# DAPule-LPC11U35-v1_1_0.net
KiCad netlist of a schematic drawn in EAGLE
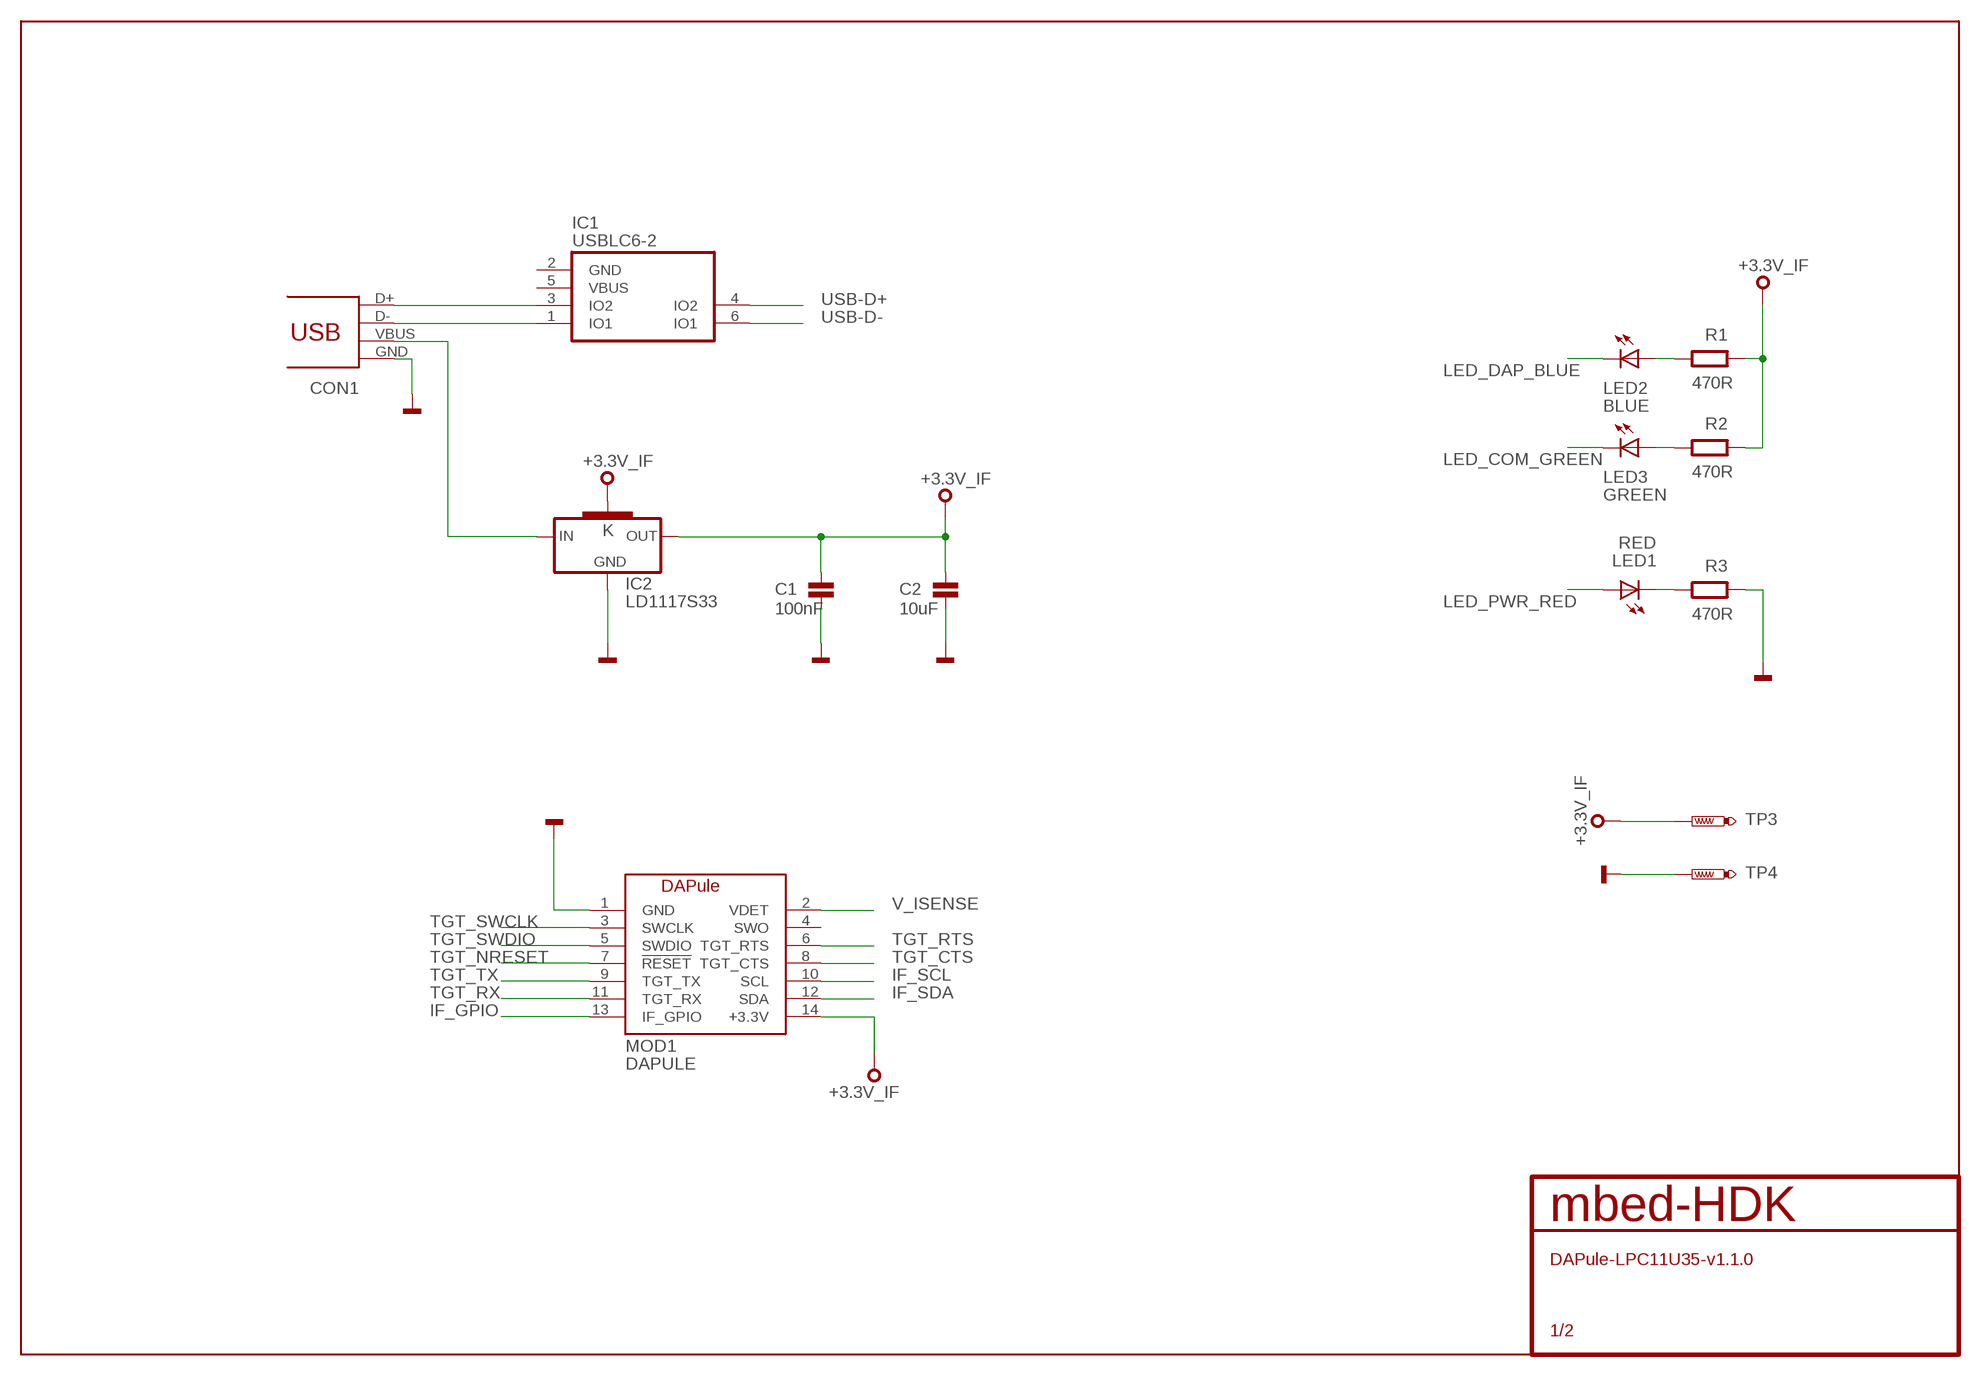
[diagram p0: schematic, sheet 1]
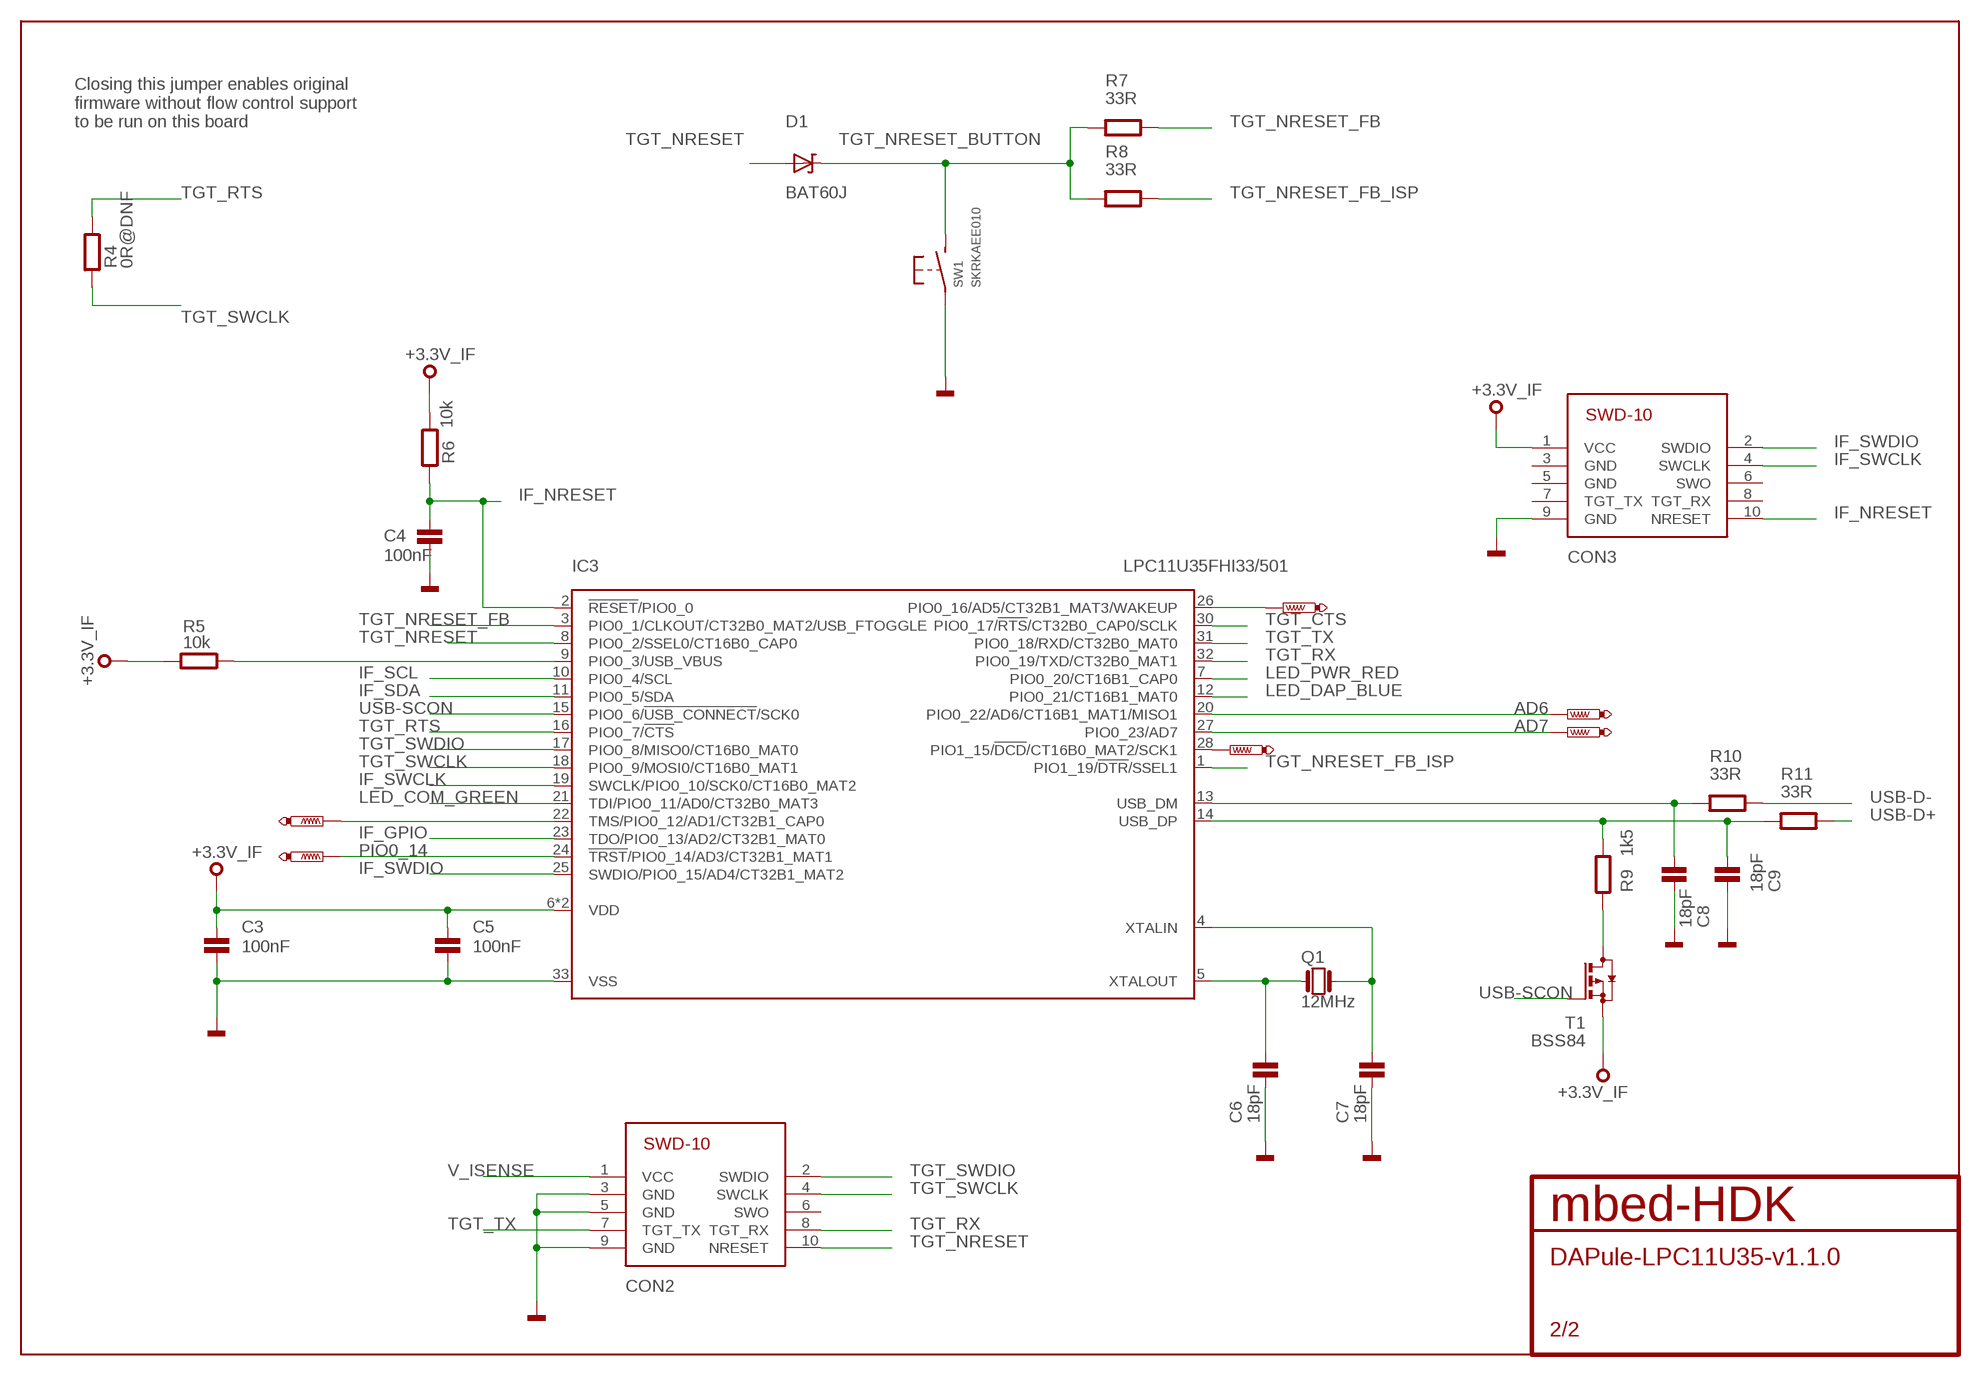
[diagram p1: schematic, sheet 2]

(export (version "E")
  (design (tool "Eeschema 10.0.6"))
  (components
    (comp (ref "C3")
      (value "100nF")
      (footprint "eagle-import:0603")
      (libsource (lib "eagle-import") (part "C0603"))
    )
    (comp (ref "C4")
      (value "100nF")
      (footprint "eagle-import:0603")
      (libsource (lib "eagle-import") (part "C0603"))
    )
    (comp (ref "C5")
      (value "100nF")
      (footprint "eagle-import:0603")
      (libsource (lib "eagle-import") (part "C0603"))
    )
    (comp (ref "C6")
      (value "18pF")
      (footprint "eagle-import:0603")
      (libsource (lib "eagle-import") (part "C0603"))
    )
    (comp (ref "C7")
      (value "18pF")
      (footprint "eagle-import:0603")
      (libsource (lib "eagle-import") (part "C0603"))
    )
    (comp (ref "C8")
      (value "18pF")
      (footprint "eagle-import:0603")
      (libsource (lib "eagle-import") (part "C0603"))
    )
    (comp (ref "C9")
      (value "18pF")
      (footprint "eagle-import:0603")
      (libsource (lib "eagle-import") (part "C0603"))
    )
    (comp (ref "CON2")
      (value "SWD-10/TC2050_SMD")
      (footprint "eagle-import:FTSH-105-02")
      (libsource (lib "eagle-import") (part "SWD-10/TC2050_SMD"))
    )
    (comp (ref "CON3")
      (value "SWD-10/TC2050_SMD")
      (footprint "eagle-import:FTSH-105-02")
      (libsource (lib "eagle-import") (part "SWD-10/TC2050_SMD"))
    )
    (comp (ref "D1")
      (value "BAT60J")
      (footprint "eagle-import:SOD323")
      (fields (field (name "MF") "STMicroelectronics"))
      (libsource (lib "eagle-import") (part "BAT60J"))
    )
    (comp (ref "IC3")
      (value "LPC11U35FHI33/501")
      (footprint "eagle-import:SOT617-3")
      (libsource (lib "eagle-import") (part "LPC11U35FHI33/501"))
    )
    (comp (ref "Q1")
      (value "12MHz")
      (footprint "eagle-import:3.2X.2.5")
      (libsource (lib "eagle-import") (part "Q_3.2X2.5"))
    )
    (comp (ref "R4")
      (value "0R@DNF")
      (footprint "eagle-import:0402@1")
      (libsource (lib "eagle-import") (part "R0402"))
    )
    (comp (ref "R5")
      (value "10k")
      (footprint "eagle-import:0603@1")
      (libsource (lib "eagle-import") (part "R0603"))
    )
    (comp (ref "R6")
      (value "10k")
      (footprint "eagle-import:0603@1")
      (libsource (lib "eagle-import") (part "R0603"))
    )
    (comp (ref "R7")
      (value "33R")
      (footprint "eagle-import:0603@1")
      (libsource (lib "eagle-import") (part "R0603"))
    )
    (comp (ref "R8")
      (value "33R")
      (footprint "eagle-import:0603@1")
      (libsource (lib "eagle-import") (part "R0603"))
    )
    (comp (ref "R9")
      (value "1k5")
      (footprint "eagle-import:0603@1")
      (libsource (lib "eagle-import") (part "R0603"))
    )
    (comp (ref "R10")
      (value "33R")
      (footprint "eagle-import:0603@1")
      (libsource (lib "eagle-import") (part "R0603"))
    )
    (comp (ref "R11")
      (value "33R")
      (footprint "eagle-import:0603@1")
      (libsource (lib "eagle-import") (part "R0603"))
    )
    (comp (ref "SW1")
      (value "SKRKAEE010")
      (footprint "eagle-import:SKRKAEE010")
      (fields (field (name "MF") "ALPS"))
      (libsource (lib "eagle-import") (part "SKRKAEE010"))
    )
    (comp (ref "T1")
      (value "BSS84")
      (footprint "eagle-import:SOT23")
      (libsource (lib "eagle-import") (part "BSS84"))
    )
    (comp (ref "TP1")
      (value "PTR1TP07R")
      (footprint "eagle-import:TP07R")
      (libsource (lib "eagle-import") (part "PTR1TP07R"))
    )
    (comp (ref "TP2")
      (value "PTR1TP07R")
      (footprint "eagle-import:TP07R")
      (libsource (lib "eagle-import") (part "PTR1TP07R"))
    )
    (comp (ref "TP5")
      (value "PTR1TP07R")
      (footprint "eagle-import:TP07R")
      (libsource (lib "eagle-import") (part "PTR1TP07R"))
    )
    (comp (ref "TP8")
      (value "PTR1TP07R")
      (footprint "eagle-import:TP07R")
      (libsource (lib "eagle-import") (part "PTR1TP07R"))
    )
    (comp (ref "TP9")
      (value "PTR1TP07R")
      (footprint "eagle-import:TP07R")
      (libsource (lib "eagle-import") (part "PTR1TP07R"))
    )
    (comp (ref "TP13")
      (value "PTR1TP07R")
      (footprint "eagle-import:TP07R")
      (libsource (lib "eagle-import") (part "PTR1TP07R"))
    )
    (comp (ref "C1")
      (value "100nF")
      (footprint "eagle-import:0603")
      (libsource (lib "eagle-import") (part "C0603"))
    )
    (comp (ref "C2")
      (value "10uF")
      (footprint "eagle-import:0603")
      (libsource (lib "eagle-import") (part "C0603"))
    )
    (comp (ref "CON1")
      (value "USB_MICROB")
      (footprint "eagle-import:MOLEX-47364-0001")
      (libsource (lib "eagle-import") (part "USB_MICROB"))
    )
    (comp (ref "IC1")
      (value "USBLC6-2SC6")
      (footprint "eagle-import:SOT23-6L")
      (libsource (lib "eagle-import") (part "USBLC6-2SC6"))
    )
    (comp (ref "IC2")
      (value "LD1117S33")
      (footprint "eagle-import:SOT223")
      (libsource (lib "eagle-import") (part "LD1117S33"))
    )
    (comp (ref "LED1")
      (value "RED")
      (footprint "eagle-import:CHIPLED_0603")
      (libsource (lib "eagle-import") (part "LED0603"))
    )
    (comp (ref "LED2")
      (value "BLUE")
      (footprint "eagle-import:CHIPLED_0603")
      (libsource (lib "eagle-import") (part "LED0603"))
    )
    (comp (ref "LED3")
      (value "GREEN")
      (footprint "eagle-import:CHIPLED_0603")
      (libsource (lib "eagle-import") (part "LED0603"))
    )
    (comp (ref "MOD1")
      (value "DAPULE")
      (footprint "eagle-import:DAPULE")
      (libsource (lib "eagle-import") (part "DAPULE"))
    )
    (comp (ref "R1")
      (value "470R")
      (footprint "eagle-import:0603@1")
      (libsource (lib "eagle-import") (part "R0603"))
    )
    (comp (ref "R2")
      (value "470R")
      (footprint "eagle-import:0603@1")
      (libsource (lib "eagle-import") (part "R0603"))
    )
    (comp (ref "R3")
      (value "470R")
      (footprint "eagle-import:0603@1")
      (libsource (lib "eagle-import") (part "R0603"))
    )
    (comp (ref "TP3")
      (value "TEST-POINT-50R-PTH")
      (footprint "eagle-import:TP50-PTH")
      (libsource (lib "eagle-import") (part "TEST-POINT-50R-PTH"))
    )
    (comp (ref "TP4")
      (value "TEST-POINT-50R-PTH")
      (footprint "eagle-import:TP50-PTH")
      (libsource (lib "eagle-import") (part "TEST-POINT-50R-PTH"))
    )
  )
  (nets
    (net (code "1") (name "+3.3V_IF") (class "Default")
      (node (ref "C1") (pin "1") (pinfunction "P$1_1") (pintype "passive"))
      (node (ref "C2") (pin "1") (pinfunction "P$1_1") (pintype "passive"))
      (node (ref "C3") (pin "1") (pinfunction "P$1_1") (pintype "passive"))
      (node (ref "C5") (pin "1") (pinfunction "P$1_1") (pintype "passive"))
      (node (ref "CON3") (pin "1") (pinfunction "VCC_1") (pintype "bidirectional"))
      (node (ref "IC2") (pin "2") (pinfunction "OUT_2") (pintype "passive"))
      (node (ref "IC2") (pin "4") (pinfunction "K_4") (pintype "passive"))
      (node (ref "IC3") (pin "29") (pinfunction "VDD_29") (pintype "passive"))
      (node (ref "IC3") (pin "6") (pinfunction "VDD_6") (pintype "passive"))
      (node (ref "MOD1") (pin "14") (pinfunction "+3.3V_14") (pintype "bidirectional"))
      (node (ref "R1") (pin "1") (pinfunction "P$1_1") (pintype "passive"))
      (node (ref "R2") (pin "1") (pinfunction "P$1_1") (pintype "passive"))
      (node (ref "R5") (pin "2") (pinfunction "P$2_2") (pintype "passive"))
      (node (ref "R6") (pin "2") (pinfunction "P$2_2") (pintype "passive"))
      (node (ref "T1") (pin "2") (pinfunction "S_2") (pintype "passive"))
      (node (ref "TP3") (pin "TP") (pinfunction "TP_TP") (pintype "input"))
    )
    (net (code "2") (name "AD6") (class "Default")
      (node (ref "IC3") (pin "20") (pinfunction "PIO0_22/AD6/CT16B1_MAT1/MISO1_20") (pintype "bidirectional"))
      (node (ref "TP9") (pin "TP") (pinfunction "TP_TP") (pintype "input"))
    )
    (net (code "3") (name "AD7") (class "Default")
      (node (ref "IC3") (pin "27") (pinfunction "PIO0_23/AD7_27") (pintype "bidirectional"))
      (node (ref "TP8") (pin "TP") (pinfunction "TP_TP") (pintype "input"))
    )
    (net (code "4") (name "GND") (class "Default")
      (node (ref "C1") (pin "2") (pinfunction "P$2_2") (pintype "passive"))
      (node (ref "C2") (pin "2") (pinfunction "P$2_2") (pintype "passive"))
      (node (ref "C3") (pin "2") (pinfunction "P$2_2") (pintype "passive"))
      (node (ref "C4") (pin "2") (pinfunction "P$2_2") (pintype "passive"))
      (node (ref "C5") (pin "2") (pinfunction "P$2_2") (pintype "passive"))
      (node (ref "C6") (pin "2") (pinfunction "P$2_2") (pintype "passive"))
      (node (ref "C7") (pin "2") (pinfunction "P$2_2") (pintype "passive"))
      (node (ref "C8") (pin "2") (pinfunction "P$2_2") (pintype "passive"))
      (node (ref "C9") (pin "2") (pinfunction "P$2_2") (pintype "passive"))
      (node (ref "CON1") (pin "GND") (pinfunction "GND_GND") (pintype "bidirectional"))
      (node (ref "CON2") (pin "3") (pinfunction "GND_3") (pintype "bidirectional"))
      (node (ref "CON2") (pin "5") (pinfunction "GND_5") (pintype "bidirectional"))
      (node (ref "CON2") (pin "9") (pinfunction "GND_9") (pintype "bidirectional"))
      (node (ref "CON3") (pin "9") (pinfunction "GND_9") (pintype "bidirectional"))
      (node (ref "IC2") (pin "1") (pinfunction "GND_1") (pintype "input"))
      (node (ref "IC3") (pin "33") (pinfunction "VSS_33") (pintype "passive"))
      (node (ref "MOD1") (pin "1") (pinfunction "GND_1") (pintype "bidirectional"))
      (node (ref "R3") (pin "1") (pinfunction "P$1_1") (pintype "passive"))
      (node (ref "SW1") (pin "P$1") (pinfunction "P_P$1") (pintype "passive"))
      (node (ref "TP4") (pin "TP") (pinfunction "TP_TP") (pintype "input"))
    )
    (net (code "5") (name "IF_GPIO") (class "Default")
      (node (ref "IC3") (pin "23") (pinfunction "TDO/PIO0_13/AD2/CT32B1_MAT0_23") (pintype "bidirectional"))
      (node (ref "MOD1") (pin "13") (pinfunction "IF_GPIO_13") (pintype "bidirectional"))
    )
    (net (code "6") (name "IF_NRESET") (class "Default")
      (node (ref "C4") (pin "1") (pinfunction "P$1_1") (pintype "passive"))
      (node (ref "CON3") (pin "10") (pinfunction "NRESET_10") (pintype "bidirectional"))
      (node (ref "IC3") (pin "2") (pinfunction "~{RESET}/PIO0_0_2") (pintype "bidirectional"))
      (node (ref "R6") (pin "1") (pinfunction "P$1_1") (pintype "passive"))
    )
    (net (code "7") (name "IF_SCL") (class "Default")
      (node (ref "IC3") (pin "10") (pinfunction "PIO0_4/SCL_10") (pintype "bidirectional"))
      (node (ref "MOD1") (pin "10") (pinfunction "SCL_10") (pintype "bidirectional"))
    )
    (net (code "8") (name "IF_SDA") (class "Default")
      (node (ref "IC3") (pin "11") (pinfunction "PIO0_5/SDA_11") (pintype "bidirectional"))
      (node (ref "MOD1") (pin "12") (pinfunction "SDA_12") (pintype "bidirectional"))
    )
    (net (code "9") (name "IF_SWCLK") (class "Default")
      (node (ref "CON3") (pin "4") (pinfunction "SWCLK_4") (pintype "bidirectional"))
      (node (ref "IC3") (pin "19") (pinfunction "SWCLK/PIO0_10/SCK0/CT16B0_MAT2_19") (pintype "bidirectional"))
    )
    (net (code "10") (name "IF_SWDIO") (class "Default")
      (node (ref "CON3") (pin "2") (pinfunction "SWDIO_2") (pintype "bidirectional"))
      (node (ref "IC3") (pin "25") (pinfunction "SWDIO/PIO0_15/AD4/CT32B1_MAT2_25") (pintype "bidirectional"))
    )
    (net (code "11") (name "LED_COM_GREEN") (class "Default")
      (node (ref "IC3") (pin "21") (pinfunction "TDI/PIO0_11/AD0/CT32B0_MAT3_21") (pintype "bidirectional"))
      (node (ref "LED3") (pin "C") (pinfunction "C_C") (pintype "passive"))
    )
    (net (code "12") (name "LED_DAP_BLUE") (class "Default")
      (node (ref "IC3") (pin "12") (pinfunction "PIO0_21/CT16B1_MAT0_12") (pintype "bidirectional"))
      (node (ref "LED2") (pin "C") (pinfunction "C_C") (pintype "passive"))
    )
    (net (code "13") (name "LED_PWR_RED") (class "Default")
      (node (ref "IC3") (pin "7") (pinfunction "PIO0_20/CT16B1_CAP0_7") (pintype "bidirectional"))
      (node (ref "LED1") (pin "A") (pinfunction "A_A") (pintype "passive"))
    )
    (net (code "14") (name "Net-(C6-P$1)") (class "Default")
      (node (ref "C6") (pin "1") (pinfunction "P$1_1") (pintype "passive"))
      (node (ref "IC3") (pin "5") (pinfunction "XTALOUT_5") (pintype "output"))
      (node (ref "Q1") (pin "P$1") (pinfunction "1_P$1") (pintype "passive"))
    )
    (net (code "15") (name "Net-(C7-P$1)") (class "Default")
      (node (ref "C7") (pin "1") (pinfunction "P$1_1") (pintype "passive"))
      (node (ref "IC3") (pin "4") (pinfunction "XTALIN_4") (pintype "input"))
      (node (ref "Q1") (pin "P$3") (pinfunction "2_P$3") (pintype "passive"))
    )
    (net (code "16") (name "Net-(C8-P$1)") (class "Default")
      (node (ref "C8") (pin "1") (pinfunction "P$1_1") (pintype "passive"))
      (node (ref "IC3") (pin "13") (pinfunction "USB_DM_13") (pintype "bidirectional"))
      (node (ref "R10") (pin "2") (pinfunction "P$2_2") (pintype "passive"))
    )
    (net (code "17") (name "Net-(C9-P$1)") (class "Default")
      (node (ref "C9") (pin "1") (pinfunction "P$1_1") (pintype "passive"))
      (node (ref "IC3") (pin "14") (pinfunction "USB_DP_14") (pintype "bidirectional"))
      (node (ref "R11") (pin "2") (pinfunction "P$2_2") (pintype "passive"))
      (node (ref "R9") (pin "2") (pinfunction "P$2_2") (pintype "passive"))
    )
    (net (code "18") (name "Net-(CON1-PadD+)") (class "Default")
      (node (ref "CON1") (pin "D+") (pinfunction "D+_D+") (pintype "bidirectional"))
      (node (ref "IC1") (pin "3") (pinfunction "IO2_3") (pintype "bidirectional"))
    )
    (net (code "19") (name "Net-(CON1-PadD-)") (class "Default")
      (node (ref "CON1") (pin "D-") (pinfunction "D-_D-") (pintype "bidirectional"))
      (node (ref "IC1") (pin "1") (pinfunction "IO1_1") (pintype "bidirectional"))
    )
    (net (code "20") (name "Net-(IC2-IN)") (class "Default")
      (node (ref "CON1") (pin "VBUS") (pinfunction "VBUS_VBUS") (pintype "bidirectional"))
      (node (ref "IC2") (pin "3") (pinfunction "IN_3") (pintype "input"))
    )
    (net (code "21") (name "Net-(IC3-PIO0_3{slash}USB_VBUS)") (class "Default")
      (node (ref "IC3") (pin "9") (pinfunction "PIO0_3/USB_VBUS_9") (pintype "bidirectional"))
      (node (ref "R5") (pin "1") (pinfunction "P$1_1") (pintype "passive"))
    )
    (net (code "22") (name "Net-(IC3-PIO0_16{slash}AD5{slash}CT32B1_MAT3{slash}WAKEUP)") (class "Default")
      (node (ref "IC3") (pin "26") (pinfunction "PIO0_16/AD5/CT32B1_MAT3/WAKEUP_26") (pintype "bidirectional"))
      (node (ref "TP2") (pin "TP") (pinfunction "TP_TP") (pintype "input"))
    )
    (net (code "23") (name "Net-(IC3-PIO1_15{slash}~{DCD}{slash}CT16B0_MAT2{slash}SCK1)") (class "Default")
      (node (ref "IC3") (pin "28") (pinfunction "PIO1_15/~{DCD}/CT16B0_MAT2/SCK1_28") (pintype "bidirectional"))
      (node (ref "TP5") (pin "TP") (pinfunction "TP_TP") (pintype "input"))
    )
    (net (code "24") (name "Net-(IC3-TMS{slash}PIO0_12{slash}AD1{slash}CT32B1_CAP0)") (class "Default")
      (node (ref "IC3") (pin "22") (pinfunction "TMS/PIO0_12/AD1/CT32B1_CAP0_22") (pintype "bidirectional"))
      (node (ref "TP1") (pin "TP") (pinfunction "TP_TP") (pintype "input"))
    )
    (net (code "25") (name "Net-(R1-P$2)") (class "Default")
      (node (ref "LED2") (pin "A") (pinfunction "A_A") (pintype "passive"))
      (node (ref "R1") (pin "2") (pinfunction "P$2_2") (pintype "passive"))
    )
    (net (code "26") (name "Net-(R2-P$2)") (class "Default")
      (node (ref "LED3") (pin "A") (pinfunction "A_A") (pintype "passive"))
      (node (ref "R2") (pin "2") (pinfunction "P$2_2") (pintype "passive"))
    )
    (net (code "27") (name "Net-(R3-P$2)") (class "Default")
      (node (ref "LED1") (pin "C") (pinfunction "C_C") (pintype "passive"))
      (node (ref "R3") (pin "2") (pinfunction "P$2_2") (pintype "passive"))
    )
    (net (code "28") (name "Net-(R9-P$1)") (class "Default")
      (node (ref "R9") (pin "1") (pinfunction "P$1_1") (pintype "passive"))
      (node (ref "T1") (pin "3") (pinfunction "D_3") (pintype "passive"))
    )
    (net (code "29") (name "PIO0_14") (class "Default")
      (node (ref "IC3") (pin "24") (pinfunction "~{TRST}/PIO0_14/AD3/CT32B1_MAT1_24") (pintype "bidirectional"))
      (node (ref "TP13") (pin "TP") (pinfunction "TP_TP") (pintype "input"))
    )
    (net (code "30") (name "TGT_CTS") (class "Default")
      (node (ref "IC3") (pin "30") (pinfunction "PIO0_17/~{RTS}/CT32B0_CAP0/SCLK_30") (pintype "bidirectional"))
      (node (ref "MOD1") (pin "8") (pinfunction "TGT_CTS_8") (pintype "bidirectional"))
    )
    (net (code "31") (name "TGT_NRESET") (class "Default")
      (node (ref "CON2") (pin "10") (pinfunction "NRESET_10") (pintype "bidirectional"))
      (node (ref "D1") (pin "A") (pinfunction "A_A") (pintype "passive"))
      (node (ref "IC3") (pin "8") (pinfunction "PIO0_2/SSEL0/CT16B0_CAP0_8") (pintype "bidirectional"))
      (node (ref "MOD1") (pin "7") (pinfunction "~{RESET}_7") (pintype "bidirectional"))
    )
    (net (code "32") (name "TGT_NRESET_BUTTON") (class "Default")
      (node (ref "D1") (pin "K") (pinfunction "K_K") (pintype "passive"))
      (node (ref "R7") (pin "2") (pinfunction "P$2_2") (pintype "passive"))
      (node (ref "R8") (pin "2") (pinfunction "P$2_2") (pintype "passive"))
      (node (ref "SW1") (pin "P$2") (pinfunction "S_P$2") (pintype "passive"))
    )
    (net (code "33") (name "TGT_NRESET_FB") (class "Default")
      (node (ref "IC3") (pin "3") (pinfunction "PIO0_1/CLKOUT/CT32B0_MAT2/USB_FTOGGLE_3") (pintype "bidirectional"))
      (node (ref "R7") (pin "1") (pinfunction "P$1_1") (pintype "passive"))
    )
    (net (code "34") (name "TGT_NRESET_FB_ISP") (class "Default")
      (node (ref "IC3") (pin "1") (pinfunction "PIO1_19/~{DTR}/SSEL1_1") (pintype "bidirectional"))
      (node (ref "R8") (pin "1") (pinfunction "P$1_1") (pintype "passive"))
    )
    (net (code "35") (name "TGT_RTS") (class "Default")
      (node (ref "IC3") (pin "16") (pinfunction "PIO0_7/~{CTS}_16") (pintype "bidirectional"))
      (node (ref "MOD1") (pin "6") (pinfunction "TGT_RTS_6") (pintype "bidirectional"))
      (node (ref "R4") (pin "2") (pinfunction "P$2_2") (pintype "passive"))
    )
    (net (code "36") (name "TGT_RX") (class "Default")
      (node (ref "CON2") (pin "8") (pinfunction "TGT_RX_8") (pintype "bidirectional"))
      (node (ref "IC3") (pin "32") (pinfunction "PIO0_19/TXD/CT32B0_MAT1_32") (pintype "bidirectional"))
      (node (ref "MOD1") (pin "11") (pinfunction "TGT_RX_11") (pintype "bidirectional"))
    )
    (net (code "37") (name "TGT_SWCLK") (class "Default")
      (node (ref "CON2") (pin "4") (pinfunction "SWCLK_4") (pintype "bidirectional"))
      (node (ref "IC3") (pin "18") (pinfunction "PIO0_9/MOSI0/CT16B0_MAT1_18") (pintype "bidirectional"))
      (node (ref "MOD1") (pin "3") (pinfunction "SWCLK_3") (pintype "bidirectional"))
      (node (ref "R4") (pin "1") (pinfunction "P$1_1") (pintype "passive"))
    )
    (net (code "38") (name "TGT_SWDIO") (class "Default")
      (node (ref "CON2") (pin "2") (pinfunction "SWDIO_2") (pintype "bidirectional"))
      (node (ref "IC3") (pin "17") (pinfunction "PIO0_8/MISO0/CT16B0_MAT0_17") (pintype "bidirectional"))
      (node (ref "MOD1") (pin "5") (pinfunction "SWDIO_5") (pintype "bidirectional"))
    )
    (net (code "39") (name "TGT_TX") (class "Default")
      (node (ref "CON2") (pin "7") (pinfunction "TGT_TX_7") (pintype "bidirectional"))
      (node (ref "IC3") (pin "31") (pinfunction "PIO0_18/RXD/CT32B0_MAT0_31") (pintype "bidirectional"))
      (node (ref "MOD1") (pin "9") (pinfunction "TGT_TX_9") (pintype "bidirectional"))
    )
    (net (code "40") (name "USB-D+") (class "Default")
      (node (ref "IC1") (pin "4") (pinfunction "IO2_4") (pintype "bidirectional"))
      (node (ref "R11") (pin "1") (pinfunction "P$1_1") (pintype "passive"))
    )
    (net (code "41") (name "USB-D-") (class "Default")
      (node (ref "IC1") (pin "6") (pinfunction "IO1_6") (pintype "bidirectional"))
      (node (ref "R10") (pin "1") (pinfunction "P$1_1") (pintype "passive"))
    )
    (net (code "42") (name "USB-SCON") (class "Default")
      (node (ref "IC3") (pin "15") (pinfunction "PIO0_6/~{USB_CONNECT}/SCK0_15") (pintype "bidirectional"))
      (node (ref "T1") (pin "1") (pinfunction "G_1") (pintype "passive"))
    )
    (net (code "43") (name "V_ISENSE") (class "Default")
      (node (ref "CON2") (pin "1") (pinfunction "VCC_1") (pintype "bidirectional"))
      (node (ref "MOD1") (pin "2") (pinfunction "VDET_2") (pintype "bidirectional"))
    )
    (net (code "44") (name "unconnected-(CON2-SWO-Pad6)") (class "Default")
      (node (ref "CON2") (pin "6") (pinfunction "SWO_6") (pintype "bidirectional"))
    )
    (net (code "45") (name "unconnected-(CON3-GND-Pad3)") (class "Default")
      (node (ref "CON3") (pin "3") (pinfunction "GND_3") (pintype "bidirectional"))
    )
    (net (code "46") (name "unconnected-(CON3-GND-Pad5)") (class "Default")
      (node (ref "CON3") (pin "5") (pinfunction "GND_5") (pintype "bidirectional"))
    )
    (net (code "47") (name "unconnected-(CON3-SWO-Pad6)") (class "Default")
      (node (ref "CON3") (pin "6") (pinfunction "SWO_6") (pintype "bidirectional"))
    )
    (net (code "48") (name "unconnected-(CON3-TGT_RX-Pad8)") (class "Default")
      (node (ref "CON3") (pin "8") (pinfunction "TGT_RX_8") (pintype "bidirectional"))
    )
    (net (code "49") (name "unconnected-(CON3-TGT_TX-Pad7)") (class "Default")
      (node (ref "CON3") (pin "7") (pinfunction "TGT_TX_7") (pintype "bidirectional"))
    )
    (net (code "50") (name "unconnected-(IC1-GND-Pad2)") (class "Default")
      (node (ref "IC1") (pin "2") (pinfunction "GND_2") (pintype "bidirectional"))
    )
    (net (code "51") (name "unconnected-(IC1-VBUS-Pad5)") (class "Default")
      (node (ref "IC1") (pin "5") (pinfunction "VBUS_5") (pintype "bidirectional"))
    )
    (net (code "52") (name "unconnected-(MOD1-SWO-Pad4)") (class "Default")
      (node (ref "MOD1") (pin "4") (pinfunction "SWO_4") (pintype "bidirectional"))
    )
  )
)
